# Sensor.net
KiCad netlist of a schematic drawn in Altium Designer
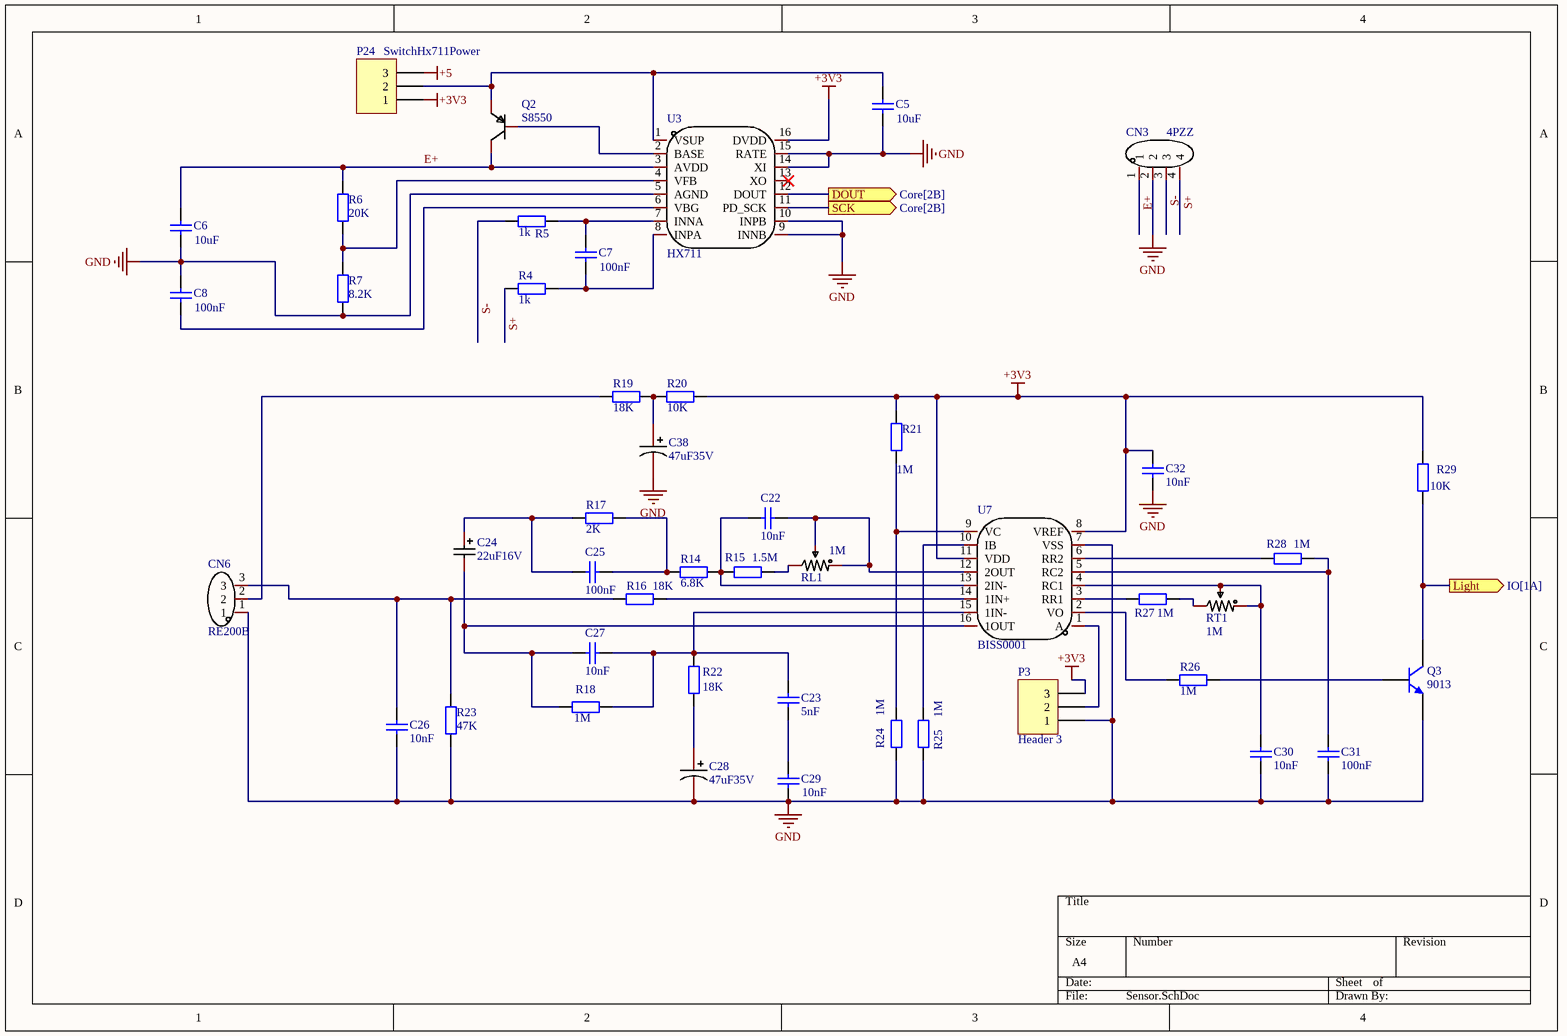
[diagram p0: Sensor.SchDoc]

(export (version "E")
  (design (tool "Eeschema 10.0.6"))
  (components
    (comp (ref "C5")
      (value "10uF")
      (footprint "6-0805_N")
      (description "Capacitor")
      (fields (field (name "Comment") "Cap") (field (name "PUBLISHER") "Altium Limited"))
      (libsource (lib "Miscellaneous Devices") (part "Cap"))
    )
    (comp (ref "C6")
      (value "10uF")
      (footprint "6-0805_N")
      (description "Capacitor")
      (fields (field (name "Comment") "Cap") (field (name "PUBLISHER") "Altium Limited"))
      (libsource (lib "Miscellaneous Devices") (part "Cap"))
    )
    (comp (ref "C7")
      (value "100nF")
      (footprint "6-0805_N")
      (description "Capacitor")
      (fields (field (name "Comment") "Cap") (field (name "PUBLISHER") "Altium Limited"))
      (libsource (lib "Miscellaneous Devices") (part "Cap"))
    )
    (comp (ref "C8")
      (value "100nF")
      (footprint "6-0805_N")
      (description "Capacitor")
      (fields (field (name "Comment") "Cap") (field (name "PUBLISHER") "Altium Limited"))
      (libsource (lib "Miscellaneous Devices") (part "Cap"))
    )
    (comp (ref "C22")
      (value "10nF")
      (footprint "6-0805_N")
      (description "Capacitor")
      (fields (field (name "Comment") "Cap") (field (name "PUBLISHER") "Altium Limited"))
      (libsource (lib "Miscellaneous Devices") (part "Cap"))
    )
    (comp (ref "C23")
      (value "5nF")
      (footprint "6-0805_N")
      (description "Capacitor")
      (fields (field (name "Comment") "Cap") (field (name "PUBLISHER") "Altium Limited"))
      (libsource (lib "Miscellaneous Devices") (part "Cap"))
    )
    (comp (ref "C24")
      (value "22uF")
      (footprint "CASE-B_3528")
      (fields
        (field (name "MANUFACTURER") "Kyocera AVX")
        (field (name "MANUFACTURER PART") "TAJB226K016RNJ")
        (field (name "TOLERANCE") "±10%")
        (field (name "NAME") "22uF16V")
      )
      (libsource (lib "22uF16VT") (part "TAJB226K016RNJ"))
    )
    (comp (ref "C25")
      (value "100nF")
      (footprint "6-0805_N")
      (description "Capacitor")
      (fields (field (name "Comment") "Cap") (field (name "PUBLISHER") "Altium Limited"))
      (libsource (lib "Miscellaneous Devices") (part "Cap"))
    )
    (comp (ref "C26")
      (value "10nF")
      (footprint "6-0805_N")
      (description "Capacitor")
      (fields (field (name "Comment") "Cap") (field (name "PUBLISHER") "Altium Limited"))
      (libsource (lib "Miscellaneous Devices") (part "Cap"))
    )
    (comp (ref "C27")
      (value "10nF")
      (footprint "6-0805_N")
      (description "Capacitor")
      (fields (field (name "Comment") "Cap") (field (name "PUBLISHER") "Altium Limited"))
      (libsource (lib "Miscellaneous Devices") (part "Cap"))
    )
    (comp (ref "C28")
      (value "47uF")
      (footprint "CAP-TH_BD5.0-P2.00-D0.5-FD-A")
      (fields
        (field (name "MANUFACTURER") "KNSCHA(科尼盛)")
        (field (name "MANUFACTURER PART") "01EC1119")
        (field (name "TOLERANCE") "±20%")
        (field (name "NAME") "47uF35V")
      )
      (libsource (lib "47uF35V") (part "01EC1119"))
    )
    (comp (ref "C29")
      (value "10nF")
      (footprint "6-0805_N")
      (description "Capacitor")
      (fields (field (name "Comment") "Cap") (field (name "PUBLISHER") "Altium Limited"))
      (libsource (lib "Miscellaneous Devices") (part "Cap"))
    )
    (comp (ref "C30")
      (value "10nF")
      (footprint "6-0805_N")
      (description "Capacitor")
      (fields (field (name "Comment") "Cap") (field (name "PUBLISHER") "Altium Limited"))
      (libsource (lib "Miscellaneous Devices") (part "Cap"))
    )
    (comp (ref "C31")
      (value "100nF")
      (footprint "6-0805_N")
      (description "Capacitor")
      (fields (field (name "Comment") "Cap") (field (name "PUBLISHER") "Altium Limited"))
      (libsource (lib "Miscellaneous Devices") (part "Cap"))
    )
    (comp (ref "C32")
      (value "10nF")
      (footprint "6-0805_N")
      (description "Capacitor")
      (fields (field (name "Comment") "Cap") (field (name "PUBLISHER") "Altium Limited"))
      (libsource (lib "Miscellaneous Devices") (part "Cap"))
    )
    (comp (ref "C38")
      (value "47uF")
      (footprint "CAP-TH_BD5.0-P2.00-D0.5-FD-A")
      (fields
        (field (name "MANUFACTURER") "KNSCHA(科尼盛)")
        (field (name "MANUFACTURER PART") "01EC1119")
        (field (name "TOLERANCE") "±20%")
        (field (name "NAME") "47uF35V")
      )
      (libsource (lib "47uF35V") (part "01EC1119"))
    )
    (comp (ref "CN3")
      (value "ZX-XH2.54-4PZZ")
      (footprint "CONN-TH_4P-P2.50_4PIN")
      (fields (field (name "MANUFACTURER") "Megastar(兆星)") (field (name "NAME") "4PZZ"))
      (libsource (lib "4PZZ") (part "ZX-XH2.54-4PZZ"))
    )
    (comp (ref "CN6")
      (value "ZX-XH2.54-3PZZ")
      (footprint "CONN-TH_3P-P2.54_2501S-3P")
      (fields (field (name "MANUFACTURER") "Megastar(兆星)") (field (name "NAME") "RE200B"))
      (libsource (lib "3PZZ") (part "ZX-XH2.54-3PZZ"))
    )
    (comp (ref "P3")
      (value "Header 3")
      (footprint "HDR1X3")
      (description "Header, 3-Pin")
      (fields (field (name "PUBLISHER") "Altium Limited"))
      (libsource (lib "Miscellaneous Connectors") (part "Header 3"))
    )
    (comp (ref "P24")
      (value "SwitchHx711Power")
      (footprint "HDR1X3")
      (description "Header, 3-Pin")
      (fields (field (name "PUBLISHER") "Altium Limited"))
      (libsource (lib "Miscellaneous Connectors") (part "Header 3"))
    )
    (comp (ref "Q2")
      (value "S8550")
      (footprint "SOT-23-3_L2.9-W1.3-P1.90-LS2.4-BR")
      (fields (field (name "MANUFACTURER") "宏迦橙") (field (name "NAME") "S8550"))
      (libsource (lib "S8550SOT-23") (part "S8550_C20069126"))
    )
    (comp (ref "Q3")
      (value "9013")
      (footprint "SOT-23-3_L2.9-W1.3-P1.90-LS2.4-BR")
      (description "NPN General Purpose Amplifier")
      (fields (field (name "PUBLISHER") "Altium Limited"))
      (libsource (lib "Miscellaneous Devices") (part "2N3904"))
    )
    (comp (ref "R4")
      (value "1k")
      (footprint "6-0805_N")
      (description "Resistor")
      (fields (field (name "Comment") "Res2") (field (name "PUBLISHER") "Altium Limited"))
      (libsource (lib "Miscellaneous Devices") (part "Res2"))
    )
    (comp (ref "R5")
      (value "1k")
      (footprint "6-0805_N")
      (description "Resistor")
      (fields (field (name "Comment") "Res2") (field (name "PUBLISHER") "Altium Limited"))
      (libsource (lib "Miscellaneous Devices") (part "Res2"))
    )
    (comp (ref "R6")
      (value "20K")
      (footprint "6-0805_N")
      (description "Resistor")
      (fields (field (name "Comment") "Res2") (field (name "PUBLISHER") "Altium Limited"))
      (libsource (lib "") (part "Res2_2"))
    )
    (comp (ref "R7")
      (value "8.2K")
      (footprint "6-0805_N")
      (description "Resistor")
      (fields (field (name "Comment") "Res2") (field (name "PUBLISHER") "Altium Limited"))
      (libsource (lib "") (part "Res2_3"))
    )
    (comp (ref "R14")
      (value "6.8K")
      (footprint "6-0805_N")
      (description "Resistor")
      (fields (field (name "Comment") "Res2") (field (name "PUBLISHER") "Altium Limited"))
      (libsource (lib "") (part "Res2_1"))
    )
    (comp (ref "R15")
      (value "1.5M")
      (footprint "6-0805_N")
      (description "Resistor")
      (fields (field (name "Comment") "Res2") (field (name "PUBLISHER") "Altium Limited"))
      (libsource (lib "") (part "Res2_1"))
    )
    (comp (ref "R16")
      (value "18K")
      (footprint "6-0805_N")
      (description "Resistor")
      (fields (field (name "Comment") "Res2") (field (name "PUBLISHER") "Altium Limited"))
      (libsource (lib "Miscellaneous Devices") (part "Res2"))
    )
    (comp (ref "R17")
      (value "2K")
      (footprint "6-0805_N")
      (description "Resistor")
      (fields (field (name "Comment") "Res2") (field (name "PUBLISHER") "Altium Limited"))
      (libsource (lib "") (part "Res2_1"))
    )
    (comp (ref "R18")
      (value "1M")
      (footprint "6-0805_N")
      (description "Resistor")
      (fields (field (name "Comment") "Res2") (field (name "PUBLISHER") "Altium Limited"))
      (libsource (lib "Miscellaneous Devices") (part "Res2"))
    )
    (comp (ref "R19")
      (value "18K")
      (footprint "6-0805_N")
      (description "Resistor")
      (fields (field (name "Comment") "Res2") (field (name "PUBLISHER") "Altium Limited"))
      (libsource (lib "") (part "Res2_1"))
    )
    (comp (ref "R20")
      (value "10K")
      (footprint "6-0805_N")
      (description "Resistor")
      (fields (field (name "Comment") "Res2") (field (name "PUBLISHER") "Altium Limited"))
      (libsource (lib "") (part "Res2_1"))
    )
    (comp (ref "R21")
      (value "1M")
      (footprint "6-0805_N")
      (description "Resistor")
      (fields (field (name "Comment") "Res2") (field (name "PUBLISHER") "Altium Limited"))
      (libsource (lib "") (part "Res2_2"))
    )
    (comp (ref "R22")
      (value "18K")
      (footprint "6-0805_N")
      (description "Resistor")
      (fields (field (name "Comment") "Res2") (field (name "PUBLISHER") "Altium Limited"))
      (libsource (lib "") (part "Res2_2"))
    )
    (comp (ref "R23")
      (value "47K")
      (footprint "6-0805_N")
      (description "Resistor")
      (fields (field (name "Comment") "Res2") (field (name "PUBLISHER") "Altium Limited"))
      (libsource (lib "") (part "Res2_2"))
    )
    (comp (ref "R24")
      (value "1M")
      (footprint "6-0805_N")
      (description "Resistor")
      (fields (field (name "Comment") "Res2") (field (name "PUBLISHER") "Altium Limited"))
      (libsource (lib "") (part "Res2_2"))
    )
    (comp (ref "R25")
      (value "1M")
      (footprint "6-0805_N")
      (description "Resistor")
      (fields (field (name "Comment") "Res2") (field (name "PUBLISHER") "Altium Limited"))
      (libsource (lib "") (part "Res2_2"))
    )
    (comp (ref "R26")
      (value "1M")
      (footprint "6-0805_N")
      (description "Resistor")
      (fields (field (name "Comment") "Res2") (field (name "PUBLISHER") "Altium Limited"))
      (libsource (lib "") (part "Res2_1"))
    )
    (comp (ref "R27")
      (value "1M")
      (footprint "6-0805_N")
      (description "Resistor")
      (fields (field (name "Comment") "Res2") (field (name "PUBLISHER") "Altium Limited"))
      (libsource (lib "") (part "Res2_1"))
    )
    (comp (ref "R28")
      (value "1M")
      (footprint "6-0805_N")
      (description "Resistor")
      (fields (field (name "Comment") "Res2") (field (name "PUBLISHER") "Altium Limited"))
      (libsource (lib "") (part "Res2_1"))
    )
    (comp (ref "R29")
      (value "10K")
      (footprint "6-0805_N")
      (description "Resistor")
      (fields (field (name "Comment") "Res2") (field (name "PUBLISHER") "Altium Limited"))
      (libsource (lib "") (part "Res2_2"))
    )
    (comp (ref "RL1")
      (value "10kΩ")
      (footprint "RES-ADJ-TH_3P-L10.0-W10.0-P2.50-L")
      (fields
        (field (name "MANUFACTURER") "BOCHEN(博晨)")
        (field (name "MANUFACTURER PART") "3296W-1-103")
        (field (name "TOLERANCE") "±10%")
        (field (name "NAME") "1M")
      )
      (libsource (lib "RL") (part "3296W-1-103"))
    )
    (comp (ref "RT1")
      (value "10kΩ")
      (footprint "RES-ADJ-TH_3P-L10.0-W10.0-P2.50-L")
      (fields
        (field (name "MANUFACTURER") "BOCHEN(博晨)")
        (field (name "MANUFACTURER PART") "3296W-1-103")
        (field (name "TOLERANCE") "±10%")
        (field (name "NAME") "1M")
      )
      (libsource (lib "RL") (part "3296W-1-103"))
    )
    (comp (ref "U3")
      (value "HX711")
      (footprint "SOP-16_L10.0-W3.9-P1.27-LS6.0-BL")
      (fields (field (name "MANUFACTURER") "AVIA(海芯科技)") (field (name "NAME") "HX711"))
      (libsource (lib "HX711") (part "HX711_C6705483"))
    )
    (comp (ref "U7")
      (value "BISS0001")
      (footprint "SOP-16_L10.0-W3.9-P1.27-LS6.0-BL")
      (fields (field (name "MANUFACTURER") "UMW(友台半导体)") (field (name "NAME") "BISS0001"))
      (libsource (lib "BISS0001") (part "BISS0001"))
    )
  )
  (nets
    (net (code "1") (name "+3V3") (class "Default")
      (node (ref "C32") (pin "1") (pinfunction "1_1") (pintype "passive"))
      (node (ref "P24") (pin "1") (pinfunction "1_1") (pintype "passive"))
      (node (ref "P3") (pin "3") (pinfunction "3_3") (pintype "passive"))
      (node (ref "R20") (pin "2") (pinfunction "2_2") (pintype "passive"))
      (node (ref "R21") (pin "1") (pinfunction "1_1") (pintype "passive"))
      (node (ref "R29") (pin "1") (pinfunction "1_1") (pintype "passive"))
      (node (ref "U3") (pin "16") (pinfunction "DVDD_16") (pintype "passive"))
      (node (ref "U7") (pin "11") (pinfunction "VDD_11") (pintype "passive"))
      (node (ref "U7") (pin "8") (pinfunction "VREF_8") (pintype "passive"))
    )
    (net (code "2") (name "+5") (class "Default")
      (node (ref "P24") (pin "3") (pinfunction "3_3") (pintype "passive"))
    )
    (net (code "3") (name "/DOUT") (class "Default")
      (node (ref "U3") (pin "12") (pinfunction "DOUT_12") (pintype "passive"))
    )
    (net (code "4") (name "/E+") (class "Default")
      (node (ref "C6") (pin "2") (pinfunction "2_2") (pintype "passive"))
      (node (ref "CN3") (pin "1") (pinfunction "1_1") (pintype "passive"))
      (node (ref "Q2") (pin "3") (pinfunction "C_3") (pintype "passive"))
      (node (ref "R6") (pin "1") (pinfunction "1_1") (pintype "passive"))
      (node (ref "U3") (pin "3") (pinfunction "AVDD_3") (pintype "passive"))
    )
    (net (code "5") (name "/Light") (class "Default")
      (node (ref "Q3") (pin "3") (pinfunction "C_3") (pintype "passive"))
      (node (ref "R29") (pin "2") (pinfunction "2_2") (pintype "passive"))
    )
    (net (code "6") (name "/S+") (class "Default")
      (node (ref "CN3") (pin "4") (pinfunction "4_4") (pintype "passive"))
      (node (ref "R4") (pin "2") (pinfunction "2_2") (pintype "passive"))
    )
    (net (code "7") (name "/S-") (class "Default")
      (node (ref "CN3") (pin "3") (pinfunction "3_3") (pintype "passive"))
      (node (ref "R5") (pin "2") (pinfunction "2_2") (pintype "passive"))
    )
    (net (code "8") (name "/SCK") (class "Default")
      (node (ref "U3") (pin "11") (pinfunction "PD_SCK_11") (pintype "passive"))
    )
    (net (code "9") (name "GND") (class "Default")
      (node (ref "C26") (pin "2") (pinfunction "2_2") (pintype "passive"))
      (node (ref "C28") (pin "2") (pinfunction "2_2") (pintype "passive"))
      (node (ref "C29") (pin "1") (pinfunction "1_1") (pintype "passive"))
      (node (ref "C30") (pin "2") (pinfunction "2_2") (pintype "passive"))
      (node (ref "C31") (pin "2") (pinfunction "2_2") (pintype "passive"))
      (node (ref "C32") (pin "2") (pinfunction "2_2") (pintype "passive"))
      (node (ref "C38") (pin "2") (pinfunction "2_2") (pintype "passive"))
      (node (ref "C5") (pin "1") (pinfunction "1_1") (pintype "passive"))
      (node (ref "C6") (pin "1") (pinfunction "1_1") (pintype "passive"))
      (node (ref "C8") (pin "2") (pinfunction "2_2") (pintype "passive"))
      (node (ref "CN3") (pin "2") (pinfunction "2_2") (pintype "passive"))
      (node (ref "CN6") (pin "1") (pinfunction "1_1") (pintype "passive"))
      (node (ref "P3") (pin "1") (pinfunction "1_1") (pintype "passive"))
      (node (ref "Q3") (pin "1") (pinfunction "E_1") (pintype "passive"))
      (node (ref "R23") (pin "2") (pinfunction "2_2") (pintype "passive"))
      (node (ref "R24") (pin "2") (pinfunction "2_2") (pintype "passive"))
      (node (ref "R25") (pin "2") (pinfunction "2_2") (pintype "passive"))
      (node (ref "R7") (pin "1") (pinfunction "1_1") (pintype "passive"))
      (node (ref "U3") (pin "10") (pinfunction "INPB_10") (pintype "passive"))
      (node (ref "U3") (pin "14") (pinfunction "XI_14") (pintype "passive"))
      (node (ref "U3") (pin "15") (pinfunction "RATE_15") (pintype "passive"))
      (node (ref "U3") (pin "5") (pinfunction "AGND_5") (pintype "passive"))
      (node (ref "U3") (pin "9") (pinfunction "INNB_9") (pintype "passive"))
      (node (ref "U7") (pin "7") (pinfunction "VSS_7") (pintype "passive"))
    )
    (net (code "10") (name "Net-(C23-Pad2)") (class "Default")
      (node (ref "C23") (pin "2") (pinfunction "2_2") (pintype "passive"))
      (node (ref "C29") (pin "2") (pinfunction "2_2") (pintype "passive"))
    )
    (net (code "11") (name "Net-(C24-Pad1)") (class "Default")
      (node (ref "C24") (pin "1") (pinfunction "1_1") (pintype "passive"))
      (node (ref "C25") (pin "1") (pinfunction "1_1") (pintype "passive"))
      (node (ref "R17") (pin "1") (pinfunction "1_1") (pintype "passive"))
    )
    (net (code "12") (name "Net-(C25-Pad2)") (class "Default")
      (node (ref "C25") (pin "2") (pinfunction "2_2") (pintype "passive"))
      (node (ref "R14") (pin "1") (pinfunction "1_1") (pintype "passive"))
      (node (ref "R17") (pin "2") (pinfunction "2_2") (pintype "passive"))
    )
    (net (code "13") (name "Net-(C26-Pad1)") (class "Default")
      (node (ref "C26") (pin "1") (pinfunction "1_1") (pintype "passive"))
      (node (ref "CN6") (pin "3") (pinfunction "3_3") (pintype "passive"))
      (node (ref "R16") (pin "2") (pinfunction "2_2") (pintype "passive"))
      (node (ref "R23") (pin "1") (pinfunction "1_1") (pintype "passive"))
    )
    (net (code "14") (name "Net-(C28-Pad1)") (class "Default")
      (node (ref "C28") (pin "1") (pinfunction "1_1") (pintype "passive"))
      (node (ref "R22") (pin "2") (pinfunction "2_2") (pintype "passive"))
    )
    (net (code "15") (name "Net-(C38-Pad1)") (class "Default")
      (node (ref "C38") (pin "1") (pinfunction "1_1") (pintype "passive"))
      (node (ref "R19") (pin "2") (pinfunction "2_2") (pintype "passive"))
      (node (ref "R20") (pin "1") (pinfunction "1_1") (pintype "passive"))
    )
    (net (code "16") (name "Net-(CN6-Pad2)") (class "Default")
      (node (ref "CN6") (pin "2") (pinfunction "2_2") (pintype "passive"))
      (node (ref "R19") (pin "1") (pinfunction "1_1") (pintype "passive"))
    )
    (net (code "17") (name "Net-(Q2-B)") (class "Default")
      (node (ref "Q2") (pin "1") (pinfunction "B_1") (pintype "passive"))
      (node (ref "U3") (pin "2") (pinfunction "BASE_2") (pintype "passive"))
    )
    (net (code "18") (name "Net-(Q2-E)") (class "Default")
      (node (ref "C5") (pin "2") (pinfunction "2_2") (pintype "passive"))
      (node (ref "P24") (pin "2") (pinfunction "2_2") (pintype "passive"))
      (node (ref "Q2") (pin "2") (pinfunction "E_2") (pintype "passive"))
      (node (ref "U3") (pin "1") (pinfunction "VSUP_1") (pintype "passive"))
    )
    (net (code "19") (name "Net-(Q3-B)") (class "Default")
      (node (ref "Q3") (pin "2") (pinfunction "B_2") (pintype "passive"))
      (node (ref "R26") (pin "2") (pinfunction "2_2") (pintype "passive"))
    )
    (net (code "20") (name "Net-(R15-Pad2)") (class "Default")
      (node (ref "R15") (pin "2") (pinfunction "2_2") (pintype "passive"))
      (node (ref "RL1") (pin "3") (pinfunction "3_3") (pintype "passive"))
    )
    (net (code "21") (name "Net-(R27-Pad2)") (class "Default")
      (node (ref "R27") (pin "2") (pinfunction "2_2") (pintype "passive"))
      (node (ref "RT1") (pin "3") (pinfunction "3_3") (pintype "passive"))
    )
    (net (code "22") (name "Net-(U3-INNA)") (class "Default")
      (node (ref "C7") (pin "2") (pinfunction "2_2") (pintype "passive"))
      (node (ref "R5") (pin "1") (pinfunction "1_1") (pintype "passive"))
      (node (ref "U3") (pin "7") (pinfunction "INNA_7") (pintype "passive"))
    )
    (net (code "23") (name "Net-(U3-INPA)") (class "Default")
      (node (ref "C7") (pin "1") (pinfunction "1_1") (pintype "passive"))
      (node (ref "R4") (pin "1") (pinfunction "1_1") (pintype "passive"))
      (node (ref "U3") (pin "8") (pinfunction "INPA_8") (pintype "passive"))
    )
    (net (code "24") (name "Net-(U3-VBG)") (class "Default")
      (node (ref "C8") (pin "1") (pinfunction "1_1") (pintype "passive"))
      (node (ref "U3") (pin "6") (pinfunction "VBG_6") (pintype "passive"))
    )
    (net (code "25") (name "Net-(U3-VFB)") (class "Default")
      (node (ref "R6") (pin "2") (pinfunction "2_2") (pintype "passive"))
      (node (ref "R7") (pin "2") (pinfunction "2_2") (pintype "passive"))
      (node (ref "U3") (pin "4") (pinfunction "VFB_4") (pintype "passive"))
    )
    (net (code "26") (name "Net-(U7-1IN+)") (class "Default")
      (node (ref "R16") (pin "1") (pinfunction "1_1") (pintype "passive"))
      (node (ref "U7") (pin "14") (pinfunction "1IN+_14") (pintype "passive"))
    )
    (net (code "27") (name "Net-(U7-1IN-)") (class "Default")
      (node (ref "C23") (pin "1") (pinfunction "1_1") (pintype "passive"))
      (node (ref "C27") (pin "1") (pinfunction "1_1") (pintype "passive"))
      (node (ref "R18") (pin "1") (pinfunction "1_1") (pintype "passive"))
      (node (ref "R22") (pin "1") (pinfunction "1_1") (pintype "passive"))
      (node (ref "U7") (pin "15") (pinfunction "1IN-_15") (pintype "passive"))
    )
    (net (code "28") (name "Net-(U7-1OUT)") (class "Default")
      (node (ref "C24") (pin "2") (pinfunction "2_2") (pintype "passive"))
      (node (ref "C27") (pin "2") (pinfunction "2_2") (pintype "passive"))
      (node (ref "R18") (pin "2") (pinfunction "2_2") (pintype "passive"))
      (node (ref "U7") (pin "16") (pinfunction "1OUT_16") (pintype "passive"))
    )
    (net (code "29") (name "Net-(U7-2IN-)") (class "Default")
      (node (ref "C22") (pin "1") (pinfunction "1_1") (pintype "passive"))
      (node (ref "R14") (pin "2") (pinfunction "2_2") (pintype "passive"))
      (node (ref "R15") (pin "1") (pinfunction "1_1") (pintype "passive"))
      (node (ref "U7") (pin "13") (pinfunction "2IN-_13") (pintype "passive"))
    )
    (net (code "30") (name "Net-(U7-2OUT)") (class "Default")
      (node (ref "C22") (pin "2") (pinfunction "2_2") (pintype "passive"))
      (node (ref "RL1") (pin "1") (pinfunction "1_1") (pintype "passive"))
      (node (ref "RL1") (pin "2") (pinfunction "2_2") (pintype "passive"))
      (node (ref "U7") (pin "12") (pinfunction "2OUT_12") (pintype "passive"))
    )
    (net (code "31") (name "Net-(U7-A)") (class "Default")
      (node (ref "P3") (pin "2") (pinfunction "2_2") (pintype "passive"))
      (node (ref "U7") (pin "1") (pinfunction "A_1") (pintype "passive"))
    )
    (net (code "32") (name "Net-(U7-IB)") (class "Default")
      (node (ref "R25") (pin "1") (pinfunction "1_1") (pintype "passive"))
      (node (ref "U7") (pin "10") (pinfunction "IB_10") (pintype "passive"))
    )
    (net (code "33") (name "Net-(U7-RC1)") (class "Default")
      (node (ref "C30") (pin "1") (pinfunction "1_1") (pintype "passive"))
      (node (ref "RT1") (pin "1") (pinfunction "1_1") (pintype "passive"))
      (node (ref "RT1") (pin "2") (pinfunction "2_2") (pintype "passive"))
      (node (ref "U7") (pin "4") (pinfunction "RC1_4") (pintype "passive"))
    )
    (net (code "34") (name "Net-(U7-RC2)") (class "Default")
      (node (ref "C31") (pin "1") (pinfunction "1_1") (pintype "passive"))
      (node (ref "R28") (pin "2") (pinfunction "2_2") (pintype "passive"))
      (node (ref "U7") (pin "5") (pinfunction "RC2_5") (pintype "passive"))
    )
    (net (code "35") (name "Net-(U7-RR1)") (class "Default")
      (node (ref "R27") (pin "1") (pinfunction "1_1") (pintype "passive"))
      (node (ref "U7") (pin "3") (pinfunction "RR1_3") (pintype "passive"))
    )
    (net (code "36") (name "Net-(U7-RR2)") (class "Default")
      (node (ref "R28") (pin "1") (pinfunction "1_1") (pintype "passive"))
      (node (ref "U7") (pin "6") (pinfunction "RR2_6") (pintype "passive"))
    )
    (net (code "37") (name "Net-(U7-VC)") (class "Default")
      (node (ref "R21") (pin "2") (pinfunction "2_2") (pintype "passive"))
      (node (ref "R24") (pin "1") (pinfunction "1_1") (pintype "passive"))
      (node (ref "U7") (pin "9") (pinfunction "VC_9") (pintype "passive"))
    )
    (net (code "38") (name "Net-(U7-VO)") (class "Default")
      (node (ref "R26") (pin "1") (pinfunction "1_1") (pintype "passive"))
      (node (ref "U7") (pin "2") (pinfunction "VO_2") (pintype "passive"))
    )
    (net (code "39") (name "unconnected-(U3-XO-Pad13)") (class "Default")
      (node (ref "U3") (pin "13") (pinfunction "XO_13") (pintype "passive+no_connect"))
    )
  )
)
